# Sheet1.net
KiCad netlist of a schematic drawn in Altium Designer
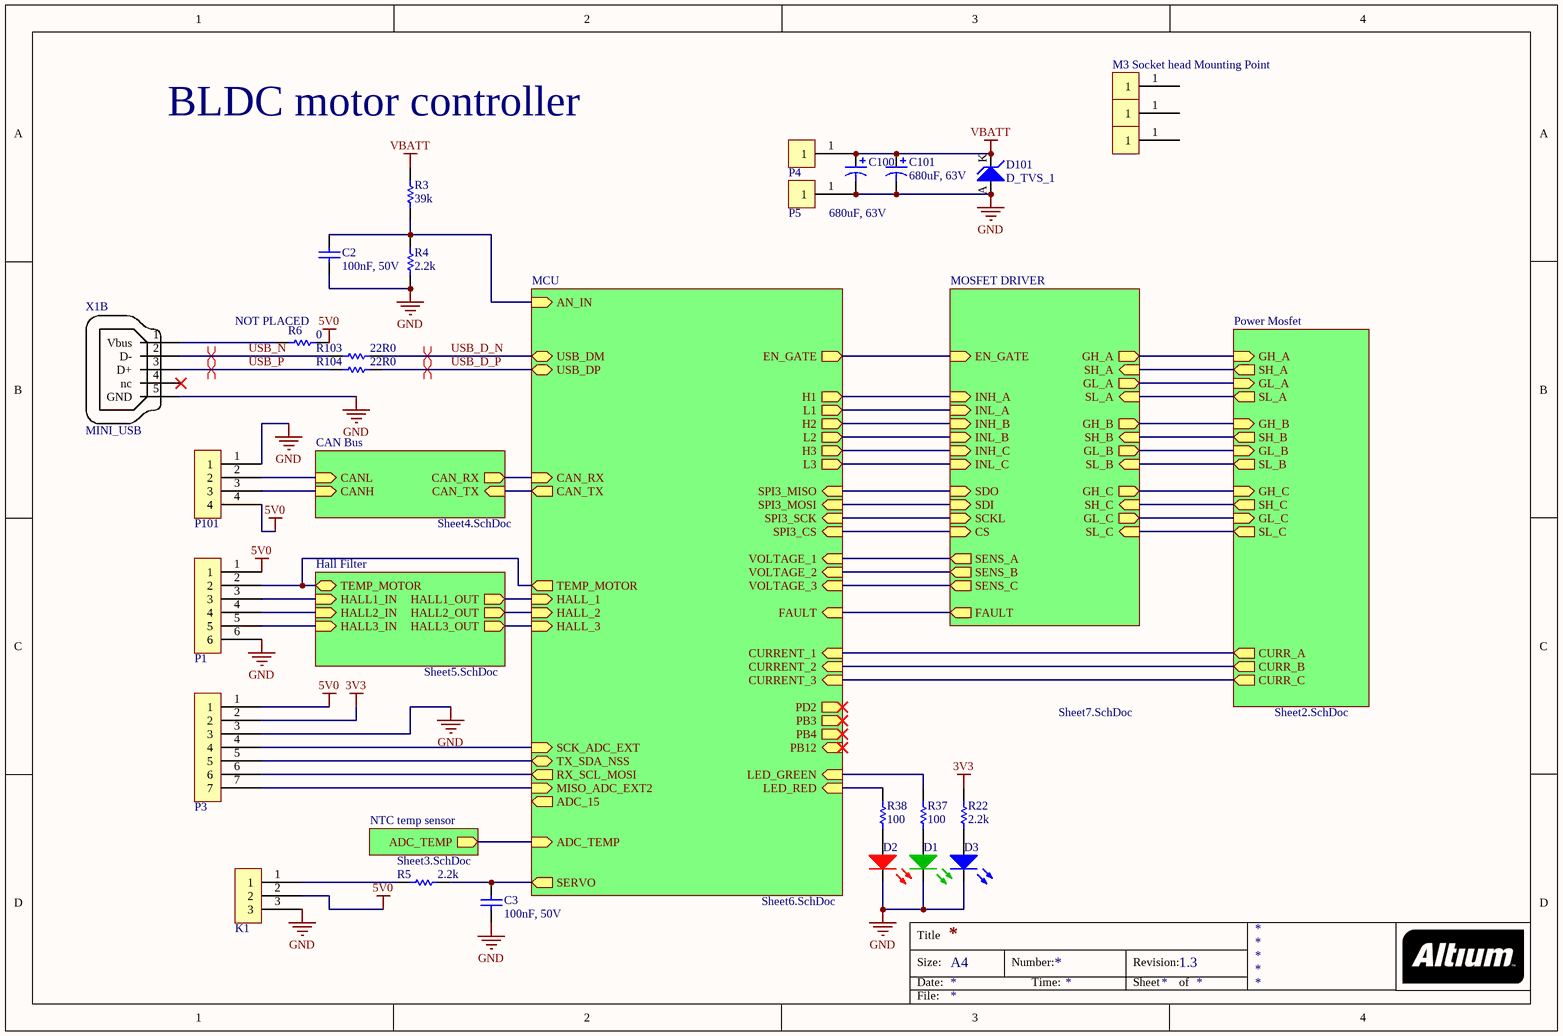
[diagram p0: Sheet1.SchDoc]

(export (version "E")
  (design (tool "Eeschema 10.0.6"))
  (components
    (comp (ref "C2")
      (value "100nF, 50V")
      (footprint "SMD-0603 Capacitor")
      (description "CAP 100n, 50V, 0603")
      (fields
        (field (name "MANUFACTURER PART NUMBER") "06035C104JAT2A")
        (field (name "MANUFACTURER") "AVX Corporation")
      )
      (libsource (lib "Master Data Link") (part "CAP"))
    )
    (comp (ref "C3")
      (value "100nF, 50V")
      (footprint "SMD-0603 Capacitor")
      (description "CAP 100n, 50V, 0603")
      (fields
        (field (name "MANUFACTURER PART NUMBER") "06035C104JAT2A")
        (field (name "MANUFACTURER") "AVX Corporation")
      )
      (libsource (lib "Master Data Link") (part "CAP"))
    )
    (comp (ref "C100")
      (value "680uF, 63V")
      (footprint "ALU CAP 16DIA 25HIGH")
      (description "680µF 63V Aluminum Capacitors Radial")
      (fields
        (field (name "MANUFACTURER PART NUMBER") "UPW1J681MHD")
        (field (name "MANUFACTURER") "Nichicon")
      )
      (libsource (lib "Master Data Link") (part "CAP_POL"))
    )
    (comp (ref "C101")
      (value "680uF, 63V")
      (footprint "ALU CAP 16DIA 25HIGH")
      (description "680µF 63V Aluminum Capacitors Radial")
      (fields
        (field (name "MANUFACTURER PART NUMBER") "UPW1J681MHD")
        (field (name "MANUFACTURER") "Nichicon")
      )
      (libsource (lib "Master Data Link") (part "CAP_POL"))
    )
    (comp (ref "D1")
      (value "LED_GREEN")
      (footprint "SMD-0603 LED GREEN")
      (description "LED Green, 0603")
      (fields (field (name "PART NUMBER") "LTST-C191KGKT") (field (name "MANUFACTURER") "Lite-On Inc."))
      (libsource (lib "Master Data Link") (part "LED_GREEN"))
    )
    (comp (ref "D2")
      (value "LED_RED")
      (footprint "SMD-0603 LED RED")
      (description "LED Red, 0603")
      (fields (field (name "PART NUMBER") "LTST-C191KRKT") (field (name "MANUFACTURER") "Lite-On Inc."))
      (libsource (lib "Master Data Link") (part "LED_RED"))
    )
    (comp (ref "D3")
      (value "LED_BLUE")
      (footprint "SMD-0603 LED BLUE")
      (description "LED Blue, 0603")
      (fields (field (name "PART NUMBER") "LBQ39GN1P1351") (field (name "MANUFACTURER") "OSRAM"))
      (libsource (lib "Master Data Link") (part "LED_BLUE"))
    )
    (comp (ref "D101")
      (value "D_TVS_1")
      (footprint "SMC-403-03")
      (description "TVS DIODE 51VWM 82.4VC SMC")
      (fields
        (field (name "MANUFACTURER PART NUMBER") "SMCJ51A")
        (field (name "MANUFACTURER") "ON Semiconductor")
      )
      (libsource (lib "Master Data Link") (part "D_TVS_1"))
    )
    (comp (ref "K1")
      (value "-")
      (footprint "HEADER 3 PIN")
      (description "Breakaway 3 pin Through hole")
      (libsource (lib "Master Data Link") (part "CON3"))
    )
    (comp (ref "M1")
      (value "M3 Socket head Mounting Point")
      (footprint "M3 Socket head")
      (libsource (lib "Master Data Link") (part "CON1"))
    )
    (comp (ref "M2")
      (value "M3 Socket head Mounting Point")
      (footprint "M3 Socket head")
      (libsource (lib "Master Data Link") (part "CON1"))
    )
    (comp (ref "M3")
      (value "M3 Socket head Mounting Point")
      (footprint "M3 Socket head")
      (libsource (lib "Master Data Link") (part "CON1"))
    )
    (comp (ref "P1")
      (value "B6B-PH-K-S(LF)(SN)")
      (footprint "JST PH TH VERT 6")
      (description "JST PH Through hole Vertical 6 Pin")
      (fields (field (name "MANUFACTURER") "JST"))
      (libsource (lib "Master Data Link") (part "CON6"))
    )
    (comp (ref "P3")
      (value "B7B-PH-K-S(LF)(SN)")
      (footprint "JST PH TH VERT 7")
      (description "JST PH Through hole Vertical 7 Pin")
      (fields (field (name "MANUFACTURER") "JST"))
      (libsource (lib "Master Data Link") (part "CON7"))
    )
    (comp (ref "P4")
      (value "-")
      (footprint "PAD1")
      (description "SMD Power landing")
      (libsource (lib "Master Data Link") (part "CON1"))
    )
    (comp (ref "P5")
      (value "-")
      (footprint "PAD1")
      (description "SMD Power landing")
      (libsource (lib "Master Data Link") (part "CON1"))
    )
    (comp (ref "P101")
      (value "B4B-PH-K-S(LF)(SN)")
      (footprint "JST PH TH VERT 4")
      (description "JST PH Through hole Vertical 4 Pin")
      (fields (field (name "MANUFACTURER") "JST"))
      (libsource (lib "Master Data Link") (part "CON4"))
    )
    (comp (ref "R3")
      (value "39k")
      (footprint "SMD-0603 Resistor")
      (description "R 39k, 0603")
      (fields
        (field (name "MANUFACTURER PART NUMBER") "ERJ-3EKF3902V")
        (field (name "MANUFACTURER") "Panasonic Electronic Components")
      )
      (libsource (lib "Master Data Link") (part "RES"))
    )
    (comp (ref "R4")
      (value "2.2k")
      (footprint "SMD-0603 Resistor")
      (description "R 2.2k, 0603")
      (fields
        (field (name "MANUFACTURER PART NUMBER") "RK73H1JTTD2201F")
        (field (name "MANUFACTURER") "KOA Speer")
      )
      (libsource (lib "Master Data Link") (part "RES"))
    )
    (comp (ref "R5")
      (value "2.2k")
      (footprint "SMD-0603 Resistor")
      (description "R 2.2k, 0603")
      (fields
        (field (name "MANUFACTURER PART NUMBER") "RK73H1JTTD2201F")
        (field (name "MANUFACTURER") "KOA Speer")
      )
      (libsource (lib "Master Data Link") (part "RES"))
    )
    (comp (ref "R6")
      (value "0")
      (footprint "SMD-0603 Resistor")
      (description "R 0 ohm, 0603")
      (fields (field (name "PLACE (YES/NO)") "NOT PLACED") (field (name "MANUFACTURER") "KOA Speer"))
      (libsource (lib "Master Data Link") (part "RES"))
    )
    (comp (ref "R22")
      (value "2.2k")
      (footprint "SMD-0603 Resistor")
      (description "R 2.2k, 0603")
      (fields
        (field (name "MANUFACTURER PART NUMBER") "RK73H1JTTD2201F")
        (field (name "MANUFACTURER") "KOA Speer")
      )
      (libsource (lib "Master Data Link") (part "RES"))
    )
    (comp (ref "R37")
      (value "100")
      (footprint "SMD-0603 Resistor")
      (description "R 100ohm, 0603")
      (fields
        (field (name "MANUFACTURER PART NUMBER") "RK73H1JTTD1000F")
        (field (name "MANUFACTURER") "KOA Speer")
      )
      (libsource (lib "Master Data Link") (part "RES"))
    )
    (comp (ref "R38")
      (value "100")
      (footprint "SMD-0603 Resistor")
      (description "R 100ohm, 0603")
      (fields
        (field (name "MANUFACTURER PART NUMBER") "RK73H1JTTD1000F")
        (field (name "MANUFACTURER") "KOA Speer")
      )
      (libsource (lib "Master Data Link") (part "RES"))
    )
    (comp (ref "R103")
      (value "22R0")
      (footprint "SMD-0603 Resistor")
      (description "R 22R, 0603")
      (fields
        (field (name "MANUFACTURER PART NUMBER") "RK73H1JTTD22R0F")
        (field (name "MANUFACTURER") "KOA Speer")
      )
      (libsource (lib "Master Data Link") (part "RES"))
    )
    (comp (ref "R104")
      (value "22R0")
      (footprint "SMD-0603 Resistor")
      (description "R 22R, 0603")
      (fields
        (field (name "MANUFACTURER PART NUMBER") "RK73H1JTTD22R0F")
        (field (name "MANUFACTURER") "KOA Speer")
      )
      (libsource (lib "Master Data Link") (part "RES"))
    )
    (comp (ref "X1B")
      (value "MINI_USB")
      (footprint "USB-MICRO B RA SMT-TH")
      (description "CONN USB MICRO B RECPT SMT R/A TH")
      (fields
        (field (name "MANUFACTURER PART NUMBER") "10118194-0001LF")
        (field (name "MANUFACTURER") "Amphenol FCI")
      )
      (libsource (lib "Master Data Link") (part "MINI_USB"))
    )
  )
  (nets
    (net (code "3") (name "/AN_IN") (class "Default")
      (node (ref "C2") (pin "1") (pinfunction "1_1") (pintype "passive"))
      (node (ref "R3") (pin "1") (pinfunction "1_1") (pintype "passive"))
      (node (ref "R4") (pin "2") (pinfunction "2_2") (pintype "passive"))
    )
    (net (code "4") (name "/CANH") (class "Default")
      (node (ref "P101") (pin "3") (pinfunction "3_3") (pintype "passive"))
    )
    (net (code "5") (name "/CANL") (class "Default")
      (node (ref "P101") (pin "2") (pinfunction "2_2") (pintype "passive"))
    )
    (net (code "23") (name "/HALL1_IN") (class "Default")
      (node (ref "P1") (pin "3") (pinfunction "3_3") (pintype "passive"))
    )
    (net (code "25") (name "/HALL2_IN") (class "Default")
      (node (ref "P1") (pin "4") (pinfunction "4_4") (pintype "passive"))
    )
    (net (code "27") (name "/HALL3_IN") (class "Default")
      (node (ref "P1") (pin "5") (pinfunction "5_5") (pintype "passive"))
    )
    (net (code "32") (name "/LED_GREEN") (class "Default")
      (node (ref "R37") (pin "2") (pinfunction "2_2") (pintype "passive"))
    )
    (net (code "33") (name "/LED_RED") (class "Default")
      (node (ref "R38") (pin "2") (pinfunction "2_2") (pintype "passive"))
    )
    (net (code "34") (name "/MISO_ADC_EXT2") (class "Default")
      (node (ref "P3") (pin "7") (pinfunction "7_7") (pintype "passive"))
    )
    (net (code "39") (name "/RX_SCL_MOSI") (class "Default")
      (node (ref "P3") (pin "6") (pinfunction "6_6") (pintype "passive"))
    )
    (net (code "41") (name "/SCK_ADC_EXT") (class "Default")
      (node (ref "P3") (pin "4") (pinfunction "4_4") (pintype "passive"))
    )
    (net (code "47") (name "/SERVO") (class "Default")
      (node (ref "C3") (pin "2") (pinfunction "2_2") (pintype "passive"))
      (node (ref "R5") (pin "2") (pinfunction "2_2") (pintype "passive"))
    )
    (net (code "54") (name "/TEMP_MOTOR") (class "Default")
      (node (ref "P1") (pin "2") (pinfunction "2_2") (pintype "passive"))
    )
    (net (code "55") (name "/TX_SDA_NSS") (class "Default")
      (node (ref "P3") (pin "5") (pinfunction "5_5") (pintype "passive"))
    )
    (net (code "56") (name "/USB_D_N") (class "Default")
      (node (ref "R103") (pin "2") (pinfunction "2_2") (pintype "passive"))
    )
    (net (code "57") (name "/USB_D_P") (class "Default")
      (node (ref "R104") (pin "2") (pinfunction "2_2") (pintype "passive"))
    )
    (net (code "58") (name "/USB_N") (class "Default")
      (node (ref "R103") (pin "1") (pinfunction "1_1") (pintype "passive"))
      (node (ref "X1B") (pin "2") (pinfunction "D-_2") (pintype "passive"))
    )
    (net (code "59") (name "/USB_P") (class "Default")
      (node (ref "R104") (pin "1") (pinfunction "1_1") (pintype "passive"))
      (node (ref "X1B") (pin "3") (pinfunction "D+_3") (pintype "passive"))
    )
    (net (code "60") (name "3V3") (class "Default")
      (node (ref "P3") (pin "2") (pinfunction "2_2") (pintype "passive"))
      (node (ref "R22") (pin "2") (pinfunction "2_2") (pintype "passive"))
    )
    (net (code "61") (name "5V0") (class "Default")
      (node (ref "K1") (pin "2") (pinfunction "2_2") (pintype "passive"))
      (node (ref "P1") (pin "1") (pinfunction "1_1") (pintype "passive"))
      (node (ref "P101") (pin "4") (pinfunction "4_4") (pintype "passive"))
      (node (ref "P3") (pin "1") (pinfunction "1_1") (pintype "passive"))
      (node (ref "R6") (pin "2") (pinfunction "2_2") (pintype "passive"))
    )
    (net (code "62") (name "GND") (class "Default")
      (node (ref "C100") (pin "2") (pinfunction "2_2") (pintype "passive"))
      (node (ref "C101") (pin "2") (pinfunction "2_2") (pintype "passive"))
      (node (ref "C2") (pin "2") (pinfunction "2_2") (pintype "passive"))
      (node (ref "C3") (pin "1") (pinfunction "1_1") (pintype "passive"))
      (node (ref "D1") (pin "2") (pinfunction "2_2") (pintype "passive"))
      (node (ref "D101") (pin "A") (pinfunction "A_A") (pintype "passive"))
      (node (ref "D2") (pin "2") (pinfunction "2_2") (pintype "passive"))
      (node (ref "D3") (pin "2") (pinfunction "2_2") (pintype "passive"))
      (node (ref "K1") (pin "3") (pinfunction "3_3") (pintype "passive"))
      (node (ref "P1") (pin "6") (pinfunction "6_6") (pintype "passive"))
      (node (ref "P101") (pin "1") (pinfunction "1_1") (pintype "passive"))
      (node (ref "P3") (pin "3") (pinfunction "3_3") (pintype "passive"))
      (node (ref "P5") (pin "1") (pinfunction "1_1") (pintype "passive"))
      (node (ref "R4") (pin "1") (pinfunction "1_1") (pintype "passive"))
      (node (ref "X1B") (pin "5") (pinfunction "GND_5") (pintype "passive"))
    )
    (net (code "63") (name "Net-(D1-Pad1)") (class "Default")
      (node (ref "D1") (pin "1") (pinfunction "1_1") (pintype "passive"))
      (node (ref "R37") (pin "1") (pinfunction "1_1") (pintype "passive"))
    )
    (net (code "64") (name "Net-(D2-Pad1)") (class "Default")
      (node (ref "D2") (pin "1") (pinfunction "1_1") (pintype "passive"))
      (node (ref "R38") (pin "1") (pinfunction "1_1") (pintype "passive"))
    )
    (net (code "65") (name "Net-(D3-Pad1)") (class "Default")
      (node (ref "D3") (pin "1") (pinfunction "1_1") (pintype "passive"))
      (node (ref "R22") (pin "1") (pinfunction "1_1") (pintype "passive"))
    )
    (net (code "66") (name "Net-(K1-Pad1)") (class "Default")
      (node (ref "K1") (pin "1") (pinfunction "1_1") (pintype "passive"))
      (node (ref "R5") (pin "1") (pinfunction "1_1") (pintype "passive"))
    )
    (net (code "67") (name "Net-(X1B-Vbus)") (class "Default")
      (node (ref "R6") (pin "1") (pinfunction "1_1") (pintype "passive"))
      (node (ref "X1B") (pin "1") (pinfunction "Vbus_1") (pintype "passive"))
    )
    (net (code "68") (name "VBATT") (class "Default")
      (node (ref "C100") (pin "1") (pinfunction "1_1") (pintype "passive"))
      (node (ref "C101") (pin "1") (pinfunction "1_1") (pintype "passive"))
      (node (ref "D101") (pin "K") (pinfunction "K_K") (pintype "passive"))
      (node (ref "P4") (pin "1") (pinfunction "1_1") (pintype "passive"))
      (node (ref "R3") (pin "2") (pinfunction "2_2") (pintype "passive"))
    )
    (net (code "69") (name "unconnected-(M1-Pad1)") (class "Default")
      (node (ref "M1") (pin "1") (pinfunction "1_1") (pintype "passive"))
    )
    (net (code "70") (name "unconnected-(M2-Pad1)") (class "Default")
      (node (ref "M2") (pin "1") (pinfunction "1_1") (pintype "passive"))
    )
    (net (code "71") (name "unconnected-(M3-Pad1)") (class "Default")
      (node (ref "M3") (pin "1") (pinfunction "1_1") (pintype "passive"))
    )
    (net (code "72") (name "unconnected-(X1B-nc-Pad4)") (class "Default")
      (node (ref "X1B") (pin "4") (pinfunction "nc_4") (pintype "passive+no_connect"))
    )
  )
)
